# LilyPad_LiPower.net
KiCad netlist of a schematic drawn in EAGLE
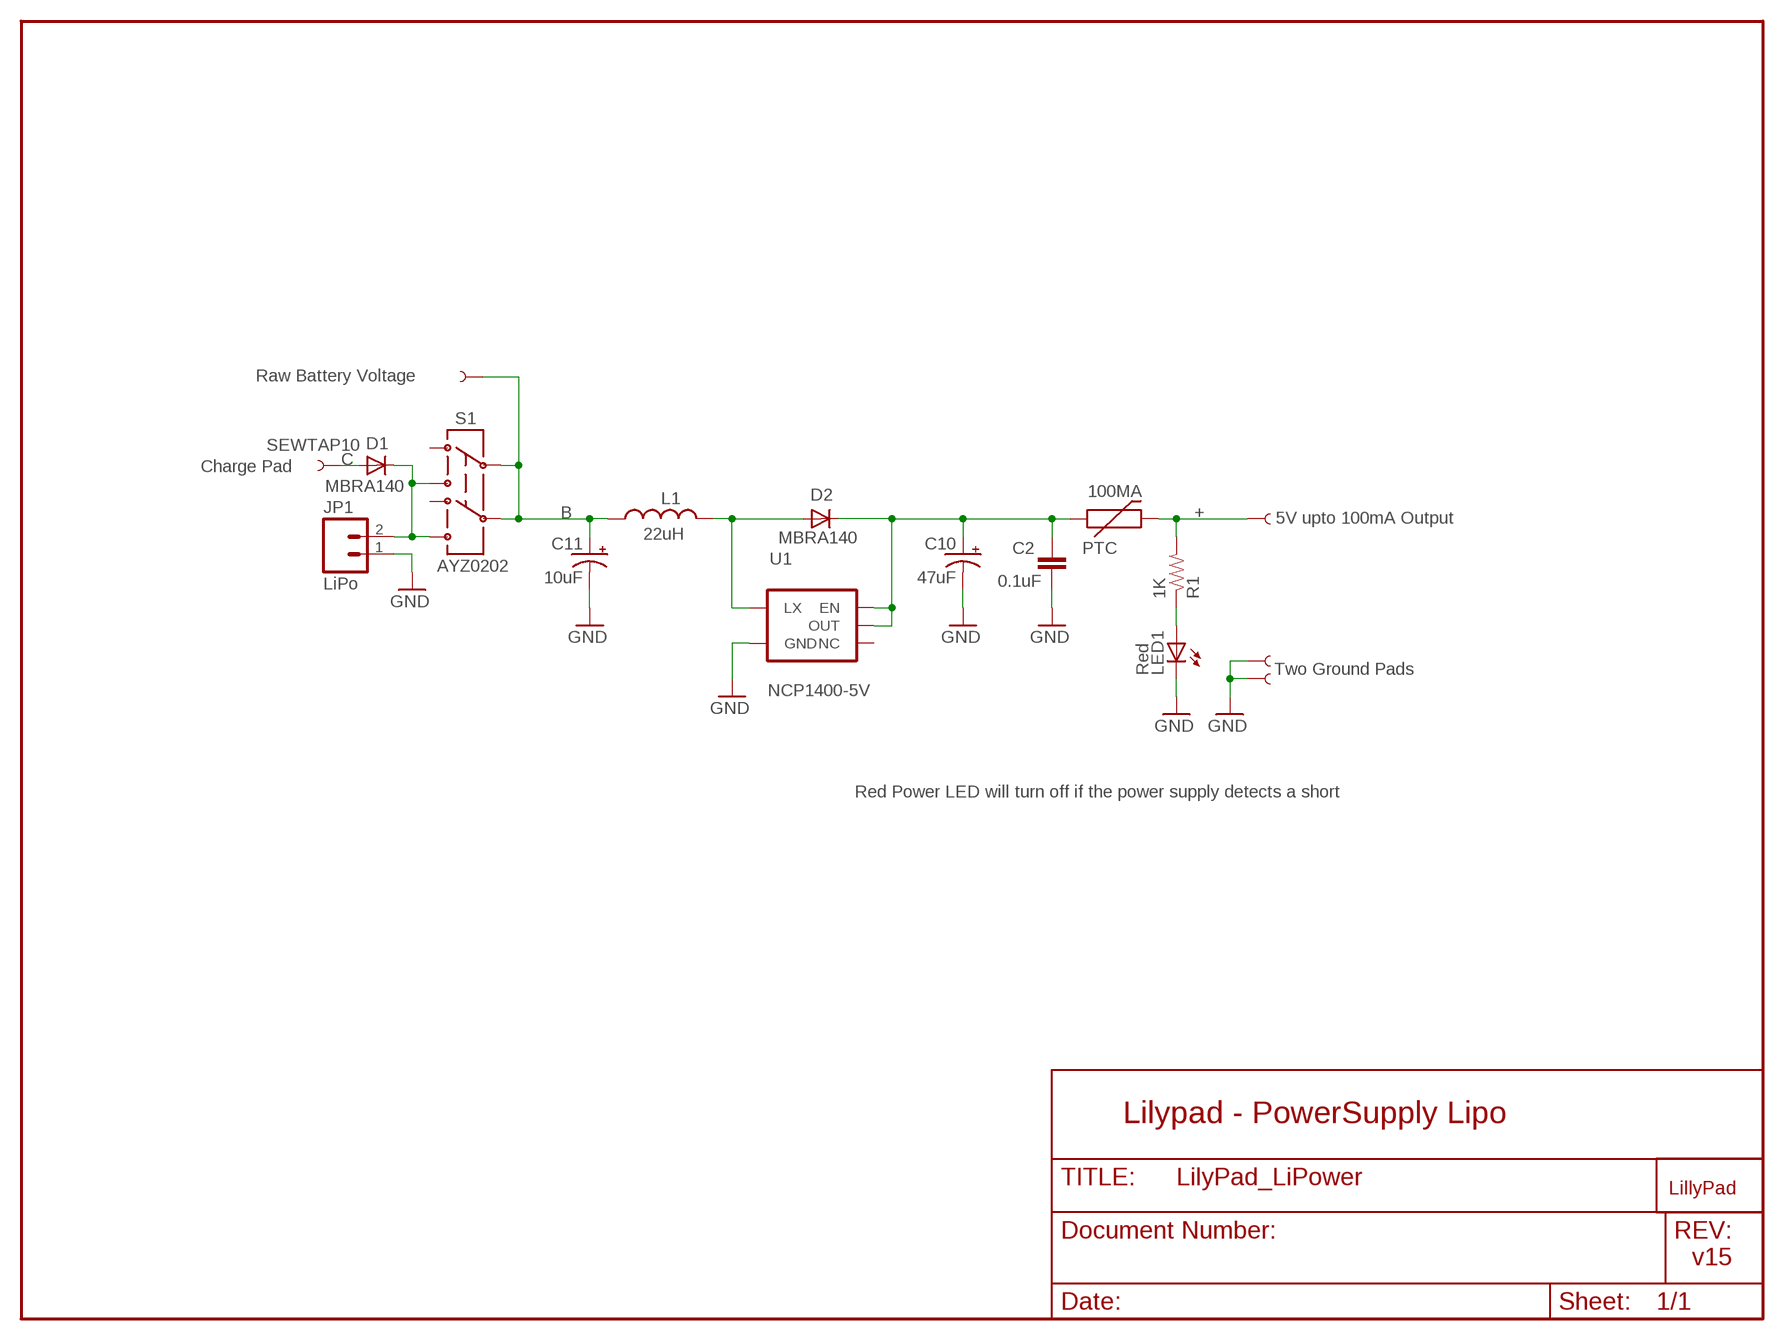
[diagram p0: schematic, sheet 1]

(export (version "E")
  (design (tool "Eeschema 10.0.6"))
  (components
    (comp (ref "100MA")
      (value "PTC")
      (footprint "eagle-import:PTC-1206")
      (libsource (lib "eagle-import") (part "PTCSMD"))
    )
    (comp (ref "C2")
      (value "0.1uF")
      (footprint "eagle-import:0603-CAP")
      (libsource (lib "eagle-import") (part "CAP0603-CAP"))
    )
    (comp (ref "C10")
      (value "47uF")
      (footprint "eagle-import:EIA3528-21")
      (libsource (lib "eagle-import") (part "CAP_POL2"))
    )
    (comp (ref "C11")
      (value "10uF")
      (footprint "eagle-import:CPOL_1206")
      (libsource (lib "eagle-import") (part "CAP_POL1206"))
    )
    (comp (ref "D1")
      (value "MBRA140")
      (footprint "eagle-import:SMA-DIODE")
      (libsource (lib "eagle-import") (part "DIODESMA"))
    )
    (comp (ref "D2")
      (value "MBRA140")
      (footprint "eagle-import:SMA-DIODE")
      (libsource (lib "eagle-import") (part "DIODESMA"))
    )
    (comp (ref "JP1")
      (value "LiPo")
      (footprint "eagle-import:JST-2-SMD")
      (libsource (lib "eagle-import") (part "M02-JST-2MM-SMT"))
    )
    (comp (ref "L1")
      (value "22uH")
      (footprint "eagle-import:CR54")
      (libsource (lib "eagle-import") (part "INDUCTORCR54"))
    )
    (comp (ref "LED1")
      (value "Red")
      (footprint "eagle-import:LED-1206")
      (libsource (lib "eagle-import") (part "LED1206"))
    )
    (comp (ref "R1")
      (value "1K")
      (footprint "eagle-import:0603-RES")
      (libsource (lib "eagle-import") (part "RESISTOR0603-RES"))
    )
    (comp (ref "S1")
      (value "AYZ0202")
      (footprint "eagle-import:AYZ0202")
      (libsource (lib "eagle-import") (part "AYZ0202"))
    )
    (comp (ref "U$1")
      (value "SEWTAP10")
      (footprint "eagle-import:PETAL-LONG-2-2SIDE")
      (libsource (lib "eagle-import") (part "SEWTAP10"))
    )
    (comp (ref "U$2")
      (value "SEWTAP10")
      (footprint "eagle-import:PETAL-LONG-2-2SIDE")
      (libsource (lib "eagle-import") (part "SEWTAP10"))
    )
    (comp (ref "U$3")
      (value "SEWTAP10")
      (footprint "eagle-import:PETAL-LONG-2-2SIDE")
      (libsource (lib "eagle-import") (part "SEWTAP10"))
    )
    (comp (ref "U$4")
      (value "SEWTAP10")
      (footprint "eagle-import:PETAL-LONG-2-2SIDE")
      (libsource (lib "eagle-import") (part "SEWTAP10"))
    )
    (comp (ref "U$5")
      (value "SEWTAP10")
      (footprint "eagle-import:PETAL-LONG-2-2SIDE")
      (libsource (lib "eagle-import") (part "SEWTAP10"))
    )
    (comp (ref "U$7")
      (value "LOGO-LPLP")
      (footprint "eagle-import:LOGO-LILYPAD")
      (libsource (lib "eagle-import") (part "LOGO-LPLP"))
    )
    (comp (ref "U1")
      (value "NCP1400-5V")
      (footprint "eagle-import:SOT23-5")
      (libsource (lib "eagle-import") (part "V_REG_NCP1400SOT23-5"))
    )
  )
  (nets
    (net (code "1") (name "/+") (class "Default")
      (node (ref "100MA") (pin "2") (pinfunction "2_2") (pintype "bidirectional"))
      (node (ref "R1") (pin "2") (pinfunction "2_2") (pintype "passive"))
      (node (ref "U$1") (pin "1") (pinfunction "1_1") (pintype "bidirectional"))
    )
    (net (code "2") (name "/B") (class "Default")
      (node (ref "C11") (pin "A") (pinfunction "+_A") (pintype "passive"))
      (node (ref "L1") (pin "P$2") (pinfunction "2_P$2") (pintype "passive"))
      (node (ref "S1") (pin "2") (pinfunction "2_2") (pintype "bidirectional"))
      (node (ref "S1") (pin "5") (pinfunction "5_5") (pintype "bidirectional"))
      (node (ref "U$3") (pin "1") (pinfunction "1_1") (pintype "bidirectional"))
    )
    (net (code "3") (name "/C") (class "Default")
      (node (ref "D1") (pin "A") (pinfunction "A_A") (pintype "passive"))
      (node (ref "U$2") (pin "1") (pinfunction "1_1") (pintype "bidirectional"))
    )
    (net (code "4") (name "GND") (class "Default")
      (node (ref "C10") (pin "C") (pinfunction "-_C") (pintype "passive"))
      (node (ref "C11") (pin "C") (pinfunction "-_C") (pintype "passive"))
      (node (ref "C2") (pin "2") (pinfunction "2_2") (pintype "passive"))
      (node (ref "JP1") (pin "1") (pinfunction "1_1") (pintype "passive"))
      (node (ref "LED1") (pin "C") (pinfunction "C_C") (pintype "passive"))
      (node (ref "U$4") (pin "1") (pinfunction "1_1") (pintype "bidirectional"))
      (node (ref "U$5") (pin "1") (pinfunction "1_1") (pintype "bidirectional"))
      (node (ref "U1") (pin "4") (pinfunction "GND_4") (pintype "input"))
    )
    (net (code "5") (name "Net-(C10-+)") (class "Default")
      (node (ref "100MA") (pin "1") (pinfunction "1_1") (pintype "bidirectional"))
      (node (ref "C10") (pin "A") (pinfunction "+_A") (pintype "passive"))
      (node (ref "C2") (pin "1") (pinfunction "1_1") (pintype "passive"))
      (node (ref "D2") (pin "C") (pinfunction "C_C") (pintype "passive"))
      (node (ref "U1") (pin "1") (pinfunction "EN_1") (pintype "input"))
      (node (ref "U1") (pin "2") (pinfunction "OUT_2") (pintype "passive"))
    )
    (net (code "6") (name "Net-(L1-1)") (class "Default")
      (node (ref "D2") (pin "A") (pinfunction "A_A") (pintype "passive"))
      (node (ref "L1") (pin "P$1") (pinfunction "1_P$1") (pintype "passive"))
      (node (ref "U1") (pin "5") (pinfunction "LX_5") (pintype "input"))
    )
    (net (code "7") (name "Net-(LED1-PadA)") (class "Default")
      (node (ref "LED1") (pin "A") (pinfunction "A_A") (pintype "passive"))
      (node (ref "R1") (pin "1") (pinfunction "1_1") (pintype "passive"))
    )
    (net (code "8") (name "Net-(S1-3)") (class "Default")
      (node (ref "D1") (pin "C") (pinfunction "C_C") (pintype "passive"))
      (node (ref "JP1") (pin "2") (pinfunction "2_2") (pintype "passive"))
      (node (ref "S1") (pin "1") (pinfunction "3_1") (pintype "bidirectional"))
      (node (ref "S1") (pin "4") (pinfunction "6_4") (pintype "bidirectional"))
    )
    (net (code "9") (name "unconnected-(S1-1-Pad3)") (class "Default")
      (node (ref "S1") (pin "3") (pinfunction "1_3") (pintype "bidirectional"))
    )
    (net (code "10") (name "unconnected-(S1-4-Pad6)") (class "Default")
      (node (ref "S1") (pin "6") (pinfunction "4_6") (pintype "bidirectional"))
    )
    (net (code "11") (name "unconnected-(U1-NC-Pad3)") (class "Default")
      (node (ref "U1") (pin "3") (pinfunction "NC_3") (pintype "input"))
    )
  )
)
